# psu.net
KiCad netlist of a schematic drawn in EAGLE
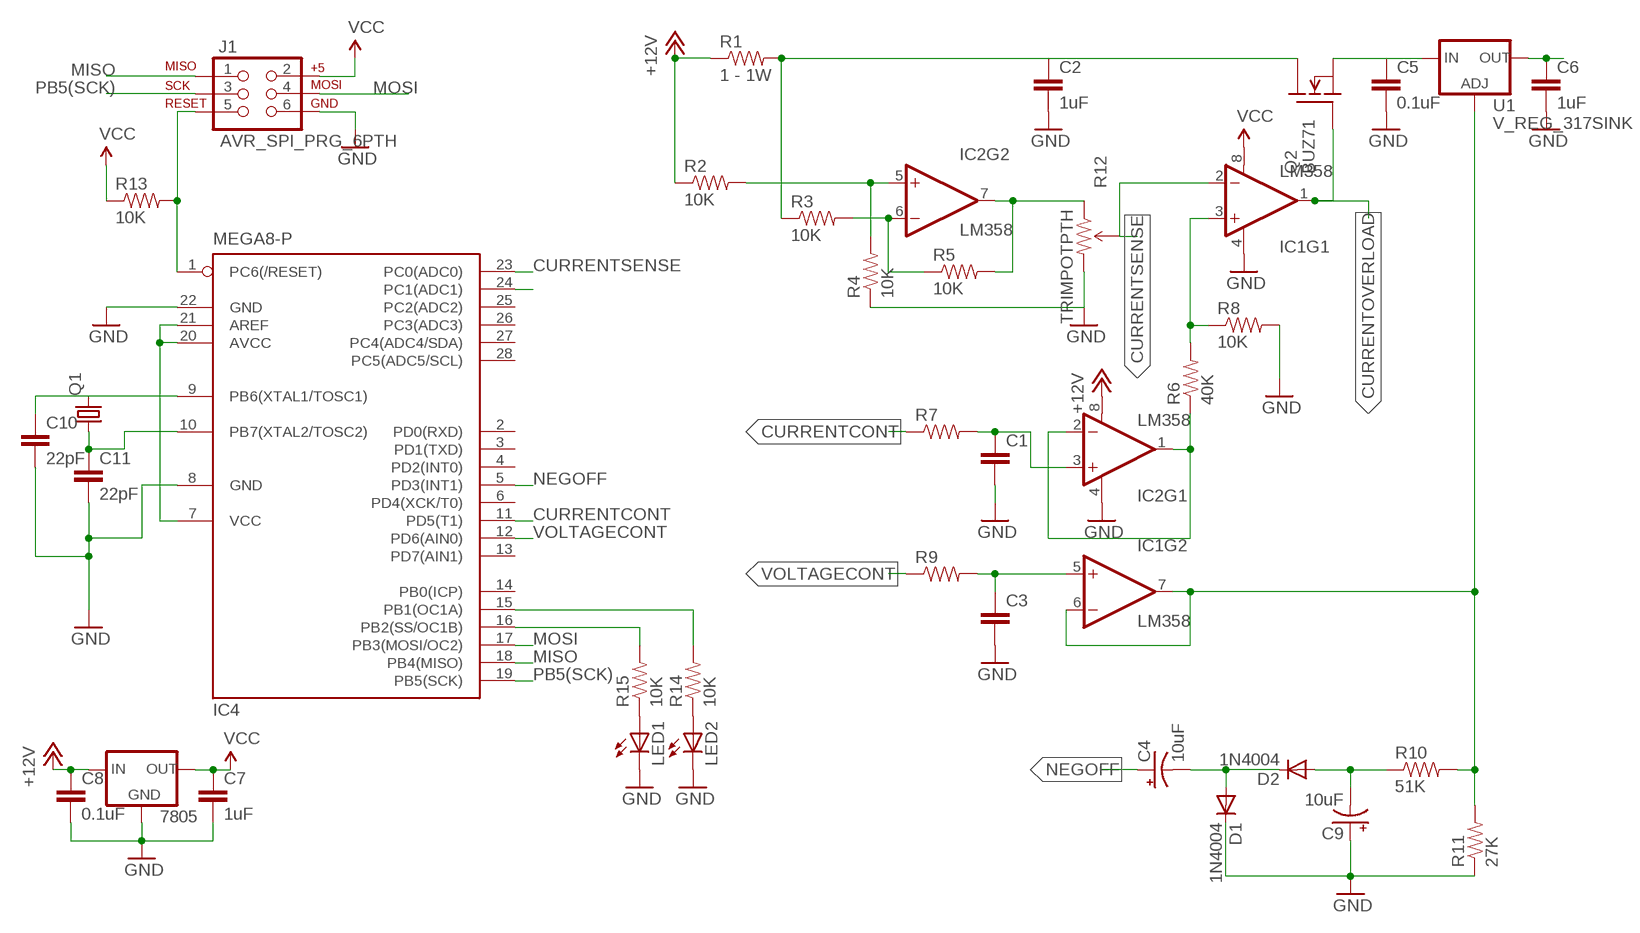
[diagram p0: schematic, sheet 1]

(export (version "E")
  (design (tool "Eeschema 10.0.6"))
  (components
    (comp (ref "7805")
      (value "V_REG_78XXSINK")
      (footprint "eagle-import:TO220-IGO")
      (libsource (lib "eagle-import") (part "V_REG_78XXSINK"))
    )
    (comp (ref "C1")
      (value "CAPPTH")
      (footprint "eagle-import:CAP-PTH-SMALL")
      (libsource (lib "eagle-import") (part "CAPPTH"))
    )
    (comp (ref "C2")
      (value "1uF")
      (footprint "eagle-import:CAP-PTH-SMALL")
      (libsource (lib "eagle-import") (part "CAPPTH"))
    )
    (comp (ref "C3")
      (value "CAPPTH")
      (footprint "eagle-import:CAP-PTH-SMALL")
      (libsource (lib "eagle-import") (part "CAPPTH"))
    )
    (comp (ref "C4")
      (value "10uF")
      (footprint "eagle-import:CPOL-RADIAL-10UF-25V")
      (libsource (lib "eagle-import") (part "CAP_POLPTH2"))
    )
    (comp (ref "C5")
      (value "0.1uF")
      (footprint "eagle-import:CAP-PTH-SMALL")
      (libsource (lib "eagle-import") (part "CAPPTH"))
    )
    (comp (ref "C6")
      (value "1uF")
      (footprint "eagle-import:CAP-PTH-SMALL")
      (libsource (lib "eagle-import") (part "CAPPTH"))
    )
    (comp (ref "C7")
      (value "1uF")
      (footprint "eagle-import:CAP-PTH-SMALL")
      (libsource (lib "eagle-import") (part "CAPPTH"))
    )
    (comp (ref "C8")
      (value "0.1uF")
      (footprint "eagle-import:CAP-PTH-SMALL")
      (libsource (lib "eagle-import") (part "CAPPTH"))
    )
    (comp (ref "C9")
      (value "10uF")
      (footprint "eagle-import:CPOL-RADIAL-10UF-25V")
      (libsource (lib "eagle-import") (part "CAP_POLPTH2"))
    )
    (comp (ref "C10")
      (value "22pF")
      (footprint "eagle-import:0805")
      (libsource (lib "eagle-import") (part "CAP0805"))
    )
    (comp (ref "C11")
      (value "22pF")
      (footprint "eagle-import:0805")
      (libsource (lib "eagle-import") (part "CAP0805"))
    )
    (comp (ref "D1")
      (value "1N4004")
      (footprint "eagle-import:DO41-10")
      (libsource (lib "eagle-import") (part "1N4004"))
    )
    (comp (ref "D2")
      (value "1N4004")
      (footprint "eagle-import:DO41-10")
      (libsource (lib "eagle-import") (part "1N4004"))
    )
    (comp (ref "IC1")
      (value "LM358")
      (footprint "eagle-import:DIP08")
      (libsource (lib "eagle-import") (part "LM358"))
    )
    (comp (ref "IC2")
      (value "LM358")
      (footprint "eagle-import:DIP08")
      (libsource (lib "eagle-import") (part "LM358"))
    )
    (comp (ref "IC4")
      (value "MEGA8-P")
      (footprint "eagle-import:DIL28-3")
      (libsource (lib "eagle-import") (part "MEGA8-P"))
    )
    (comp (ref "J1")
      (value "AVR_SPI_PRG_6PTH")
      (footprint "eagle-import:2X3")
      (libsource (lib "eagle-import") (part "AVR_SPI_PRG_6PTH"))
    )
    (comp (ref "LED1")
      (value "LED5MM")
      (footprint "eagle-import:LED5MM")
      (libsource (lib "eagle-import") (part "LED5MM"))
    )
    (comp (ref "LED2")
      (value "LED5MM")
      (footprint "eagle-import:LED5MM")
      (libsource (lib "eagle-import") (part "LED5MM"))
    )
    (comp (ref "Q1")
      (value "CRYSTALHC49UP")
      (footprint "eagle-import:HC49UP")
      (libsource (lib "eagle-import") (part "CRYSTALHC49UP"))
    )
    (comp (ref "Q2")
      (value "BUZ71")
      (footprint "eagle-import:TO220")
      (libsource (lib "eagle-import") (part "BUZ71"))
    )
    (comp (ref "R1")
      (value "1 - 1W")
      (footprint "eagle-import:AXIAL-0.4")
      (libsource (lib "eagle-import") (part "RESISTORPTH-1/4W"))
    )
    (comp (ref "R2")
      (value "10K")
      (footprint "eagle-import:AXIAL-0.4")
      (libsource (lib "eagle-import") (part "RESISTORPTH-1/4W"))
    )
    (comp (ref "R3")
      (value "10K")
      (footprint "eagle-import:AXIAL-0.4")
      (libsource (lib "eagle-import") (part "RESISTORPTH-1/4W"))
    )
    (comp (ref "R4")
      (value "10K")
      (footprint "eagle-import:AXIAL-0.4")
      (libsource (lib "eagle-import") (part "RESISTORPTH-1/4W"))
    )
    (comp (ref "R5")
      (value "10K")
      (footprint "eagle-import:AXIAL-0.4")
      (libsource (lib "eagle-import") (part "RESISTORPTH-1/4W"))
    )
    (comp (ref "R6")
      (value "40K")
      (footprint "eagle-import:AXIAL-0.4")
      (libsource (lib "eagle-import") (part "RESISTORPTH-1/4W"))
    )
    (comp (ref "R7")
      (value "RESISTORPTH-1/4W")
      (footprint "eagle-import:AXIAL-0.4")
      (libsource (lib "eagle-import") (part "RESISTORPTH-1/4W"))
    )
    (comp (ref "R8")
      (value "10K")
      (footprint "eagle-import:AXIAL-0.4")
      (libsource (lib "eagle-import") (part "RESISTORPTH-1/4W"))
    )
    (comp (ref "R9")
      (value "RESISTORPTH-1/4W")
      (footprint "eagle-import:AXIAL-0.4")
      (libsource (lib "eagle-import") (part "RESISTORPTH-1/4W"))
    )
    (comp (ref "R10")
      (value "51K")
      (footprint "eagle-import:AXIAL-0.4")
      (libsource (lib "eagle-import") (part "RESISTORPTH-1/4W"))
    )
    (comp (ref "R11")
      (value "27K")
      (footprint "eagle-import:AXIAL-0.4")
      (libsource (lib "eagle-import") (part "RESISTORPTH-1/4W"))
    )
    (comp (ref "R12")
      (value "TRIMPOTPTH")
      (footprint "eagle-import:TRIM_POT_PTH")
      (libsource (lib "eagle-import") (part "TRIMPOTPTH"))
    )
    (comp (ref "R13")
      (value "10K")
      (footprint "eagle-import:0805")
      (libsource (lib "eagle-import") (part "SparkFun-Resistors_RESISTOR0805-RES"))
    )
    (comp (ref "R14")
      (value "10K")
      (footprint "eagle-import:AXIAL-0.4")
      (libsource (lib "eagle-import") (part "RESISTORPTH-1/4W"))
    )
    (comp (ref "R15")
      (value "10K")
      (footprint "eagle-import:AXIAL-0.4")
      (libsource (lib "eagle-import") (part "RESISTORPTH-1/4W"))
    )
    (comp (ref "U1")
      (value "V_REG_317SINK")
      (footprint "eagle-import:TO220-ADJ")
      (libsource (lib "eagle-import") (part "V_REG_317SINK"))
    )
  )
  (nets
    (net (code "1") (name "+12V") (class "Default")
      (node (ref "7805") (pin "IN") (pinfunction "IN_IN") (pintype "input"))
      (node (ref "C8") (pin "1") (pinfunction "1_1") (pintype "passive"))
      (node (ref "IC2") (pin "8") (pinfunction "V+_8") (pintype "power_in"))
      (node (ref "R1") (pin "P$1") (pinfunction "1_P$1") (pintype "passive"))
      (node (ref "R2") (pin "P$1") (pinfunction "1_P$1") (pintype "passive"))
    )
    (net (code "2") (name "/MISO") (class "Default")
      (node (ref "IC4") (pin "18") (pinfunction "PB4(MISO)_18") (pintype "bidirectional"))
      (node (ref "J1") (pin "1") (pinfunction "1_1") (pintype "passive"))
    )
    (net (code "3") (name "/MOSI") (class "Default")
      (node (ref "IC4") (pin "17") (pinfunction "PB3(MOSI/OC2)_17") (pintype "bidirectional"))
      (node (ref "J1") (pin "4") (pinfunction "4_4") (pintype "passive"))
    )
    (net (code "4") (name "/PB5(SCK)") (class "Default")
      (node (ref "IC4") (pin "19") (pinfunction "PB5(SCK)_19") (pintype "bidirectional"))
      (node (ref "J1") (pin "3") (pinfunction "3_3") (pintype "passive"))
    )
    (net (code "5") (name "CURRENTCONT") (class "Default")
      (node (ref "IC4") (pin "11") (pinfunction "PD5(T1)_11") (pintype "bidirectional"))
      (node (ref "R7") (pin "P$1") (pinfunction "1_P$1") (pintype "passive"))
    )
    (net (code "6") (name "CURRENTOVERLOAD") (class "Default")
      (node (ref "IC1") (pin "1") (pinfunction "OUT_1") (pintype "output"))
      (node (ref "IC4") (pin "24") (pinfunction "PC1(ADC1)_24") (pintype "bidirectional"))
      (node (ref "Q2") (pin "1") (pinfunction "G_1") (pintype "passive"))
    )
    (net (code "7") (name "CURRENTSENSE") (class "Default")
      (node (ref "IC1") (pin "2") (pinfunction "-IN_2") (pintype "input"))
      (node (ref "IC4") (pin "23") (pinfunction "PC0(ADC0)_23") (pintype "bidirectional"))
      (node (ref "R12") (pin "2") (pinfunction "WIPER_2") (pintype "passive"))
    )
    (net (code "8") (name "GND") (class "Default")
      (node (ref "7805") (pin "GND") (pinfunction "GND_GND") (pintype "input"))
      (node (ref "C1") (pin "2") (pinfunction "2_2") (pintype "passive"))
      (node (ref "C10") (pin "2") (pinfunction "2_2") (pintype "passive"))
      (node (ref "C11") (pin "2") (pinfunction "2_2") (pintype "passive"))
      (node (ref "C2") (pin "2") (pinfunction "2_2") (pintype "passive"))
      (node (ref "C3") (pin "2") (pinfunction "2_2") (pintype "passive"))
      (node (ref "C5") (pin "2") (pinfunction "2_2") (pintype "passive"))
      (node (ref "C6") (pin "2") (pinfunction "2_2") (pintype "passive"))
      (node (ref "C7") (pin "2") (pinfunction "2_2") (pintype "passive"))
      (node (ref "C8") (pin "2") (pinfunction "2_2") (pintype "passive"))
      (node (ref "C9") (pin "1") (pinfunction "+_1") (pintype "passive"))
      (node (ref "D1") (pin "C") (pinfunction "C_C") (pintype "passive"))
      (node (ref "IC1") (pin "4") (pinfunction "V-_4") (pintype "power_in"))
      (node (ref "IC2") (pin "4") (pinfunction "V-_4") (pintype "power_in"))
      (node (ref "IC4") (pin "22") (pinfunction "GND_22") (pintype "power_in"))
      (node (ref "IC4") (pin "8") (pinfunction "GND_8") (pintype "power_in"))
      (node (ref "J1") (pin "6") (pinfunction "6_6") (pintype "passive"))
      (node (ref "LED1") (pin "K") (pinfunction "C_K") (pintype "passive"))
      (node (ref "LED2") (pin "K") (pinfunction "C_K") (pintype "passive"))
      (node (ref "R11") (pin "P$1") (pinfunction "1_P$1") (pintype "passive"))
      (node (ref "R12") (pin "3") (pinfunction "CW_3") (pintype "passive"))
      (node (ref "R4") (pin "P$1") (pinfunction "1_P$1") (pintype "passive"))
      (node (ref "R8") (pin "P$2") (pinfunction "2_P$2") (pintype "passive"))
    )
    (net (code "9") (name "NEGOFF") (class "Default")
      (node (ref "C4") (pin "1") (pinfunction "+_1") (pintype "passive"))
      (node (ref "IC4") (pin "5") (pinfunction "PD3(INT1)_5") (pintype "bidirectional"))
    )
    (net (code "10") (name "Net-(C4--)") (class "Default")
      (node (ref "C4") (pin "2") (pinfunction "-_2") (pintype "passive"))
      (node (ref "D1") (pin "A") (pinfunction "A_A") (pintype "passive"))
      (node (ref "D2") (pin "C") (pinfunction "C_C") (pintype "passive"))
    )
    (net (code "11") (name "Net-(C6-Pad1)") (class "Default")
      (node (ref "C6") (pin "1") (pinfunction "1_1") (pintype "passive"))
      (node (ref "U1") (pin "OUT") (pinfunction "OUT_OUT") (pintype "output"))
    )
    (net (code "12") (name "Net-(C9--)") (class "Default")
      (node (ref "C9") (pin "2") (pinfunction "-_2") (pintype "passive"))
      (node (ref "D2") (pin "A") (pinfunction "A_A") (pintype "passive"))
      (node (ref "R10") (pin "P$1") (pinfunction "1_P$1") (pintype "passive"))
    )
    (net (code "13") (name "Net-(IC1A-+IN)") (class "Default")
      (node (ref "IC1") (pin "3") (pinfunction "+IN_3") (pintype "input"))
      (node (ref "R6") (pin "P$2") (pinfunction "2_P$2") (pintype "passive"))
      (node (ref "R8") (pin "P$1") (pinfunction "1_P$1") (pintype "passive"))
    )
    (net (code "14") (name "Net-(IC1B-+IN)") (class "Default")
      (node (ref "C3") (pin "1") (pinfunction "1_1") (pintype "passive"))
      (node (ref "IC1") (pin "5") (pinfunction "+IN_5") (pintype "input"))
      (node (ref "R9") (pin "P$2") (pinfunction "2_P$2") (pintype "passive"))
    )
    (net (code "15") (name "Net-(IC1B--IN)") (class "Default")
      (node (ref "IC1") (pin "6") (pinfunction "-IN_6") (pintype "input"))
      (node (ref "IC1") (pin "7") (pinfunction "OUT_7") (pintype "output"))
      (node (ref "R10") (pin "P$2") (pinfunction "2_P$2") (pintype "passive"))
      (node (ref "R11") (pin "P$2") (pinfunction "2_P$2") (pintype "passive"))
      (node (ref "U1") (pin "ADJ") (pinfunction "ADJ_ADJ") (pintype "input"))
    )
    (net (code "16") (name "Net-(IC2A-+IN)") (class "Default")
      (node (ref "C1") (pin "1") (pinfunction "1_1") (pintype "passive"))
      (node (ref "IC2") (pin "3") (pinfunction "+IN_3") (pintype "input"))
      (node (ref "R7") (pin "P$2") (pinfunction "2_P$2") (pintype "passive"))
    )
    (net (code "17") (name "Net-(IC2A--IN)") (class "Default")
      (node (ref "IC2") (pin "1") (pinfunction "OUT_1") (pintype "output"))
      (node (ref "IC2") (pin "2") (pinfunction "-IN_2") (pintype "input"))
      (node (ref "R6") (pin "P$1") (pinfunction "1_P$1") (pintype "passive"))
    )
    (net (code "18") (name "Net-(IC2B-+IN)") (class "Default")
      (node (ref "IC2") (pin "5") (pinfunction "+IN_5") (pintype "input"))
      (node (ref "R2") (pin "P$2") (pinfunction "2_P$2") (pintype "passive"))
      (node (ref "R4") (pin "P$2") (pinfunction "2_P$2") (pintype "passive"))
    )
    (net (code "19") (name "Net-(IC2B--IN)") (class "Default")
      (node (ref "IC2") (pin "6") (pinfunction "-IN_6") (pintype "input"))
      (node (ref "R3") (pin "P$2") (pinfunction "2_P$2") (pintype "passive"))
      (node (ref "R5") (pin "P$1") (pinfunction "1_P$1") (pintype "passive"))
    )
    (net (code "20") (name "Net-(IC2B-OUT)") (class "Default")
      (node (ref "IC2") (pin "7") (pinfunction "OUT_7") (pintype "output"))
      (node (ref "R12") (pin "1") (pinfunction "CCW_1") (pintype "passive"))
      (node (ref "R5") (pin "P$2") (pinfunction "2_P$2") (pintype "passive"))
    )
    (net (code "21") (name "Net-(IC4-AREF)") (class "Default")
      (node (ref "IC4") (pin "20") (pinfunction "AVCC_20") (pintype "power_in"))
      (node (ref "IC4") (pin "21") (pinfunction "AREF_21") (pintype "passive"))
      (node (ref "IC4") (pin "7") (pinfunction "VCC_7") (pintype "power_in"))
    )
    (net (code "22") (name "Net-(IC4-PB1(OC1A))") (class "Default")
      (node (ref "IC4") (pin "15") (pinfunction "PB1(OC1A)_15") (pintype "bidirectional"))
      (node (ref "R14") (pin "P$2") (pinfunction "2_P$2") (pintype "passive"))
    )
    (net (code "23") (name "Net-(IC4-PB2(SS{slash}OC1B))") (class "Default")
      (node (ref "IC4") (pin "16") (pinfunction "PB2(SS/OC1B)_16") (pintype "bidirectional"))
      (node (ref "R15") (pin "P$2") (pinfunction "2_P$2") (pintype "passive"))
    )
    (net (code "24") (name "Net-(IC4-PB6(XTAL1{slash}TOSC1))") (class "Default")
      (node (ref "C10") (pin "1") (pinfunction "1_1") (pintype "passive"))
      (node (ref "IC4") (pin "9") (pinfunction "PB6(XTAL1/TOSC1)_9") (pintype "bidirectional"))
      (node (ref "Q1") (pin "2") (pinfunction "2_2") (pintype "passive"))
    )
    (net (code "25") (name "Net-(IC4-PB7(XTAL2{slash}TOSC2))") (class "Default")
      (node (ref "C11") (pin "1") (pinfunction "1_1") (pintype "passive"))
      (node (ref "IC4") (pin "10") (pinfunction "PB7(XTAL2/TOSC2)_10") (pintype "bidirectional"))
      (node (ref "Q1") (pin "1") (pinfunction "1_1") (pintype "passive"))
    )
    (net (code "26") (name "Net-(IC4-PC6({slash}RESET))") (class "Default")
      (node (ref "IC4") (pin "1") (pinfunction "PC6(/RESET)_1") (pintype "bidirectional"))
      (node (ref "J1") (pin "5") (pinfunction "5_5") (pintype "passive"))
      (node (ref "R13") (pin "2") (pinfunction "2_2") (pintype "passive"))
    )
    (net (code "27") (name "Net-(Q2-D)") (class "Default")
      (node (ref "C2") (pin "1") (pinfunction "1_1") (pintype "passive"))
      (node (ref "Q2") (pin "2") (pinfunction "D_2") (pintype "passive"))
      (node (ref "R1") (pin "P$2") (pinfunction "2_P$2") (pintype "passive"))
      (node (ref "R3") (pin "P$1") (pinfunction "1_P$1") (pintype "passive"))
    )
    (net (code "28") (name "Net-(Q2-S)") (class "Default")
      (node (ref "C5") (pin "1") (pinfunction "1_1") (pintype "passive"))
      (node (ref "Q2") (pin "3") (pinfunction "S_3") (pintype "passive"))
      (node (ref "U1") (pin "IN") (pinfunction "IN_IN") (pintype "input"))
    )
    (net (code "29") (name "Net-(R14-1)") (class "Default")
      (node (ref "LED2") (pin "A") (pinfunction "A_A") (pintype "passive"))
      (node (ref "R14") (pin "P$1") (pinfunction "1_P$1") (pintype "passive"))
    )
    (net (code "30") (name "Net-(R15-1)") (class "Default")
      (node (ref "LED1") (pin "A") (pinfunction "A_A") (pintype "passive"))
      (node (ref "R15") (pin "P$1") (pinfunction "1_P$1") (pintype "passive"))
    )
    (net (code "31") (name "VCC") (class "Default")
      (node (ref "7805") (pin "OUT") (pinfunction "OUT_OUT") (pintype "output"))
      (node (ref "C7") (pin "1") (pinfunction "1_1") (pintype "passive"))
      (node (ref "IC1") (pin "8") (pinfunction "V+_8") (pintype "power_in"))
      (node (ref "J1") (pin "2") (pinfunction "2_2") (pintype "passive"))
      (node (ref "R13") (pin "1") (pinfunction "1_1") (pintype "passive"))
    )
    (net (code "32") (name "VOLTAGECONT") (class "Default")
      (node (ref "IC4") (pin "12") (pinfunction "PD6(AIN0)_12") (pintype "bidirectional"))
      (node (ref "R9") (pin "P$1") (pinfunction "1_P$1") (pintype "passive"))
    )
    (net (code "33") (name "unconnected-(IC4-PB0(ICP)-Pad14)") (class "Default")
      (node (ref "IC4") (pin "14") (pinfunction "PB0(ICP)_14") (pintype "bidirectional"))
    )
    (net (code "34") (name "unconnected-(IC4-PC2(ADC2)-Pad25)") (class "Default")
      (node (ref "IC4") (pin "25") (pinfunction "PC2(ADC2)_25") (pintype "bidirectional"))
    )
    (net (code "35") (name "unconnected-(IC4-PC3(ADC3)-Pad26)") (class "Default")
      (node (ref "IC4") (pin "26") (pinfunction "PC3(ADC3)_26") (pintype "bidirectional"))
    )
    (net (code "36") (name "unconnected-(IC4-PC4(ADC4{slash}SDA)-Pad27)") (class "Default")
      (node (ref "IC4") (pin "27") (pinfunction "PC4(ADC4/SDA)_27") (pintype "bidirectional"))
    )
    (net (code "37") (name "unconnected-(IC4-PC5(ADC5{slash}SCL)-Pad28)") (class "Default")
      (node (ref "IC4") (pin "28") (pinfunction "PC5(ADC5/SCL)_28") (pintype "bidirectional"))
    )
    (net (code "38") (name "unconnected-(IC4-PD0(RXD)-Pad2)") (class "Default")
      (node (ref "IC4") (pin "2") (pinfunction "PD0(RXD)_2") (pintype "bidirectional"))
    )
    (net (code "39") (name "unconnected-(IC4-PD1(TXD)-Pad3)") (class "Default")
      (node (ref "IC4") (pin "3") (pinfunction "PD1(TXD)_3") (pintype "bidirectional"))
    )
    (net (code "40") (name "unconnected-(IC4-PD2(INT0)-Pad4)") (class "Default")
      (node (ref "IC4") (pin "4") (pinfunction "PD2(INT0)_4") (pintype "bidirectional"))
    )
    (net (code "41") (name "unconnected-(IC4-PD4(XCK{slash}T0)-Pad6)") (class "Default")
      (node (ref "IC4") (pin "6") (pinfunction "PD4(XCK/T0)_6") (pintype "bidirectional"))
    )
    (net (code "42") (name "unconnected-(IC4-PD7(AIN1)-Pad13)") (class "Default")
      (node (ref "IC4") (pin "13") (pinfunction "PD7(AIN1)_13") (pintype "bidirectional"))
    )
  )
)
